# Filter-12.net
KiCad netlist of a schematic drawn in Altium Designer
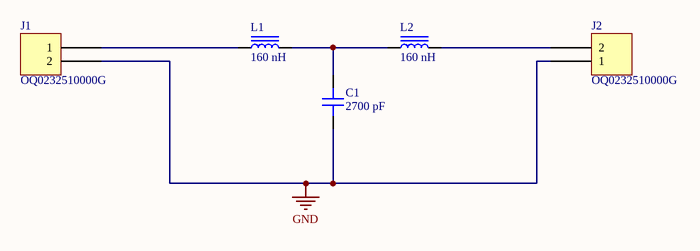
[diagram p0: Filter-12.SchDoc]

(export (version "E")
  (design (tool "Eeschema 10.0.6"))
  (components
    (comp (ref "C1")
      (value "2700 pF")
      (footprint "CAP 0603_1608")
      (description "CAP CER 2700PF 25V NP0 0603")
      (fields (field (name "PART NUMBER") "C0603C272F3GAC7867") (field (name "MANUFACTURER") "KEMET"))
      (libsource (lib "Celestial Altium Library - altium_library") (part "Capacitor"))
    )
    (comp (ref "J1")
      (value "OQ0232510000G")
      (footprint "FCI 06-381-2PIN")
      (description "TERM BLOCK HDR 2POS 90DEG 3.81MM")
      (fields (field (name "MANUFACTURER") "Amphenol Anytek"))
      (libsource (lib "") (part "2 Pin_1"))
    )
    (comp (ref "J2")
      (value "OQ0232510000G")
      (footprint "FCI 06-381-2PIN")
      (description "TERM BLOCK HDR 2POS 90DEG 3.81MM")
      (fields (field (name "MANUFACTURER") "Amphenol Anytek"))
      (libsource (lib "Celestial Altium Library - altium_library") (part "2 Pin"))
    )
    (comp (ref "L1")
      (value "160 nH")
      (footprint "IND 0402_1005 RF WW")
      (description "FIXED IND 160NH 480MA 330MOHM SM")
      (fields
        (field (name "PART NUMBER") "LQW15CNR16J00D")
        (field (name "MANUFACTURER") "Murata Electronics")
      )
      (libsource (lib "Celestial Altium Library - altium_library") (part "Inductor"))
    )
    (comp (ref "L2")
      (value "160 nH")
      (footprint "IND 0402_1005 RF WW")
      (description "FIXED IND 160NH 480MA 330MOHM SM")
      (fields
        (field (name "PART NUMBER") "LQW15CNR16J00D")
        (field (name "MANUFACTURER") "Murata Electronics")
      )
      (libsource (lib "Celestial Altium Library - altium_library") (part "Inductor"))
    )
  )
  (nets
    (net (code "1") (name "GND") (class "Default")
      (node (ref "C1") (pin "1") (pinfunction "1_1") (pintype "passive"))
      (node (ref "J1") (pin "2") (pinfunction "2_2") (pintype "passive"))
      (node (ref "J2") (pin "1") (pinfunction "1_1") (pintype "passive"))
    )
    (net (code "2") (name "Net-(C1-Pad2)") (class "Default")
      (node (ref "C1") (pin "2") (pinfunction "2_2") (pintype "passive"))
      (node (ref "L1") (pin "2") (pinfunction "2_2") (pintype "passive"))
      (node (ref "L2") (pin "1") (pinfunction "1_1") (pintype "passive"))
    )
    (net (code "3") (name "Net-(J1-Pad1)") (class "Default")
      (node (ref "J1") (pin "1") (pinfunction "1_1") (pintype "passive"))
      (node (ref "L1") (pin "1") (pinfunction "1_1") (pintype "passive"))
    )
    (net (code "4") (name "Net-(J2-Pad2)") (class "Default")
      (node (ref "J2") (pin "2") (pinfunction "2_2") (pintype "passive"))
      (node (ref "L2") (pin "2") (pinfunction "2_2") (pintype "passive"))
    )
  )
)
